# QFN-8_1_4x1_2_Breakout.net
KiCad netlist of a schematic drawn in EAGLE
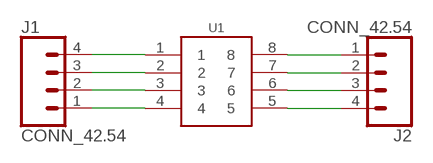
[diagram p0: schematic, sheet 1]

(export (version "E")
  (design (tool "Eeschema 10.0.6"))
  (components
    (comp (ref "J1")
      (value "CONN_42.54")
      (footprint "eagle-import:1X04")
      (libsource (lib "eagle-import") (part "CONN_42.54"))
    )
    (comp (ref "J2")
      (value "CONN_42.54")
      (footprint "eagle-import:1X04")
      (libsource (lib "eagle-import") (part "CONN_42.54"))
    )
    (comp (ref "U1")
      (value "GEN_8QFN_1.4X1.2")
      (footprint "eagle-import:UQFN-8_1.4X1.2")
      (libsource (lib "eagle-import") (part "GEN_8QFN_1.4X1.2"))
    )
  )
  (nets
    (net (code "1") (name "Net-(J1-Pad1)") (class "Default")
      (node (ref "J1") (pin "1") (pinfunction "1_1") (pintype "passive"))
      (node (ref "U1") (pin "4") (pinfunction "4_4") (pintype "bidirectional"))
    )
    (net (code "2") (name "Net-(J1-Pad2)") (class "Default")
      (node (ref "J1") (pin "2") (pinfunction "2_2") (pintype "passive"))
      (node (ref "U1") (pin "3") (pinfunction "3_3") (pintype "bidirectional"))
    )
    (net (code "3") (name "Net-(J1-Pad3)") (class "Default")
      (node (ref "J1") (pin "3") (pinfunction "3_3") (pintype "passive"))
      (node (ref "U1") (pin "2") (pinfunction "2_2") (pintype "bidirectional"))
    )
    (net (code "4") (name "Net-(J1-Pad4)") (class "Default")
      (node (ref "J1") (pin "4") (pinfunction "4_4") (pintype "passive"))
      (node (ref "U1") (pin "1") (pinfunction "1_1") (pintype "bidirectional"))
    )
    (net (code "5") (name "Net-(J2-Pad1)") (class "Default")
      (node (ref "J2") (pin "1") (pinfunction "1_1") (pintype "passive"))
      (node (ref "U1") (pin "8") (pinfunction "8_8") (pintype "bidirectional"))
    )
    (net (code "6") (name "Net-(J2-Pad2)") (class "Default")
      (node (ref "J2") (pin "2") (pinfunction "2_2") (pintype "passive"))
      (node (ref "U1") (pin "7") (pinfunction "7_7") (pintype "bidirectional"))
    )
    (net (code "7") (name "Net-(J2-Pad3)") (class "Default")
      (node (ref "J2") (pin "3") (pinfunction "3_3") (pintype "passive"))
      (node (ref "U1") (pin "6") (pinfunction "6_6") (pintype "bidirectional"))
    )
    (net (code "8") (name "Net-(J2-Pad4)") (class "Default")
      (node (ref "J2") (pin "4") (pinfunction "4_4") (pintype "passive"))
      (node (ref "U1") (pin "5") (pinfunction "5_5") (pintype "bidirectional"))
    )
  )
)
